# Shc_Encoder_Optic_Sensor.net
KiCad netlist of a schematic drawn in Altium Designer
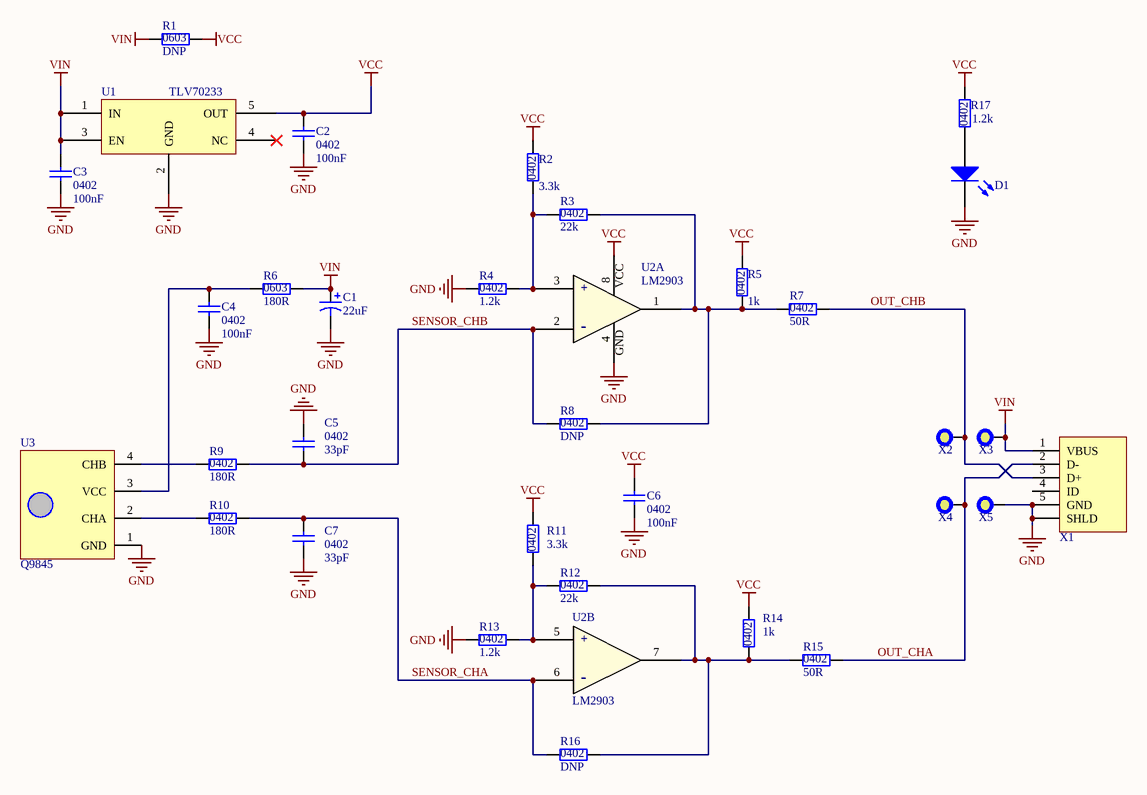
[diagram p0: Shc_Encoder_Optic_Sensor.SchDoc]

(export (version "E")
  (design (tool "Eeschema 10.0.6"))
  (components
    (comp (ref "C1")
      (value "22uF")
      (footprint "TCAP SMA")
      (description "Tantal Capacitor SMA")
      (fields (field (name "Comment") "TCAP CASE A"))
      (libsource (lib "CAP") (part "TCAP CASE A"))
    )
    (comp (ref "C2")
      (value "100nF")
      (footprint "C0402-h0.5-O")
      (description "Multilayer ceramic capacitors  0402")
      (fields
        (field (name "CASE") "0402")
        (field (name "Comment") "Ceramic Capacitor X7R 10% 50V")
        (field (name "DESIGNER") "Crom")
      )
      (libsource (lib "CAP") (part "Cap CER 0402 S"))
    )
    (comp (ref "C3")
      (value "100nF")
      (footprint "C0402-h0.5-O")
      (description "Multilayer ceramic capacitors  0402")
      (fields
        (field (name "CASE") "0402")
        (field (name "Comment") "Ceramic Capacitor X7R 10% 50V")
        (field (name "DESIGNER") "Crom")
      )
      (libsource (lib "CAP") (part "Cap CER 0402 S"))
    )
    (comp (ref "C4")
      (value "100nF")
      (footprint "C0402-h0.5-O")
      (description "Multilayer ceramic capacitors  0402")
      (fields
        (field (name "CASE") "0402")
        (field (name "Comment") "Ceramic Capacitor X7R 10% 50V")
        (field (name "DESIGNER") "Crom")
      )
      (libsource (lib "CAP") (part "Cap CER 0402 S"))
    )
    (comp (ref "C5")
      (value "33pF")
      (footprint "C0402-h0.5-O")
      (description "Multilayer ceramic capacitors  0402")
      (fields
        (field (name "CASE") "0402")
        (field (name "Comment") "Ceramic Capacitor X7R 10% 50V")
        (field (name "DESIGNER") "Crom")
      )
      (libsource (lib "CAP") (part "Cap CER 0402 S"))
    )
    (comp (ref "C6")
      (value "100nF")
      (footprint "C0402-h0.5-O")
      (description "Multilayer ceramic capacitors  0402")
      (fields
        (field (name "CASE") "0402")
        (field (name "Comment") "Ceramic Capacitor X7R 10% 50V")
        (field (name "DESIGNER") "Crom")
      )
      (libsource (lib "CAP") (part "Cap CER 0402 S"))
    )
    (comp (ref "C7")
      (value "33pF")
      (footprint "C0402-h0.5-O")
      (description "Multilayer ceramic capacitors  0402")
      (fields
        (field (name "CASE") "0402")
        (field (name "Comment") "Ceramic Capacitor X7R 10% 50V")
        (field (name "DESIGNER") "Crom")
      )
      (libsource (lib "CAP") (part "Cap CER 0402 S"))
    )
    (comp (ref "D1")
      (value "LED 0603")
      (footprint "LED 0603_RED")
      (description "Typical SMT LED")
      (libsource (lib "OPTO") (part "LED 0603"))
    )
    (comp (ref "R1")
      (value "DNP")
      (footprint "R0603")
      (description "Chip Resistor 0603 (1608)")
      (fields
        (field (name "CASE") "0603")
        (field (name "Comment") "Thick Film Resistor 0603 5%")
        (field (name "DESIGNER") "Crom")
      )
      (libsource (lib "RES") (part "Res 0603"))
    )
    (comp (ref "R2")
      (value "3.3k")
      (footprint "R0402-O")
      (description "Chip Resistor 0402 (1005) 1/16W")
      (fields
        (field (name "CASE") "0402")
        (field (name "Comment") "Thick Film Resistor 0402 5%")
        (field (name "DESIGNER") "Crom")
      )
      (libsource (lib "") (part "Res 0402_1"))
    )
    (comp (ref "R3")
      (value "22k")
      (footprint "R0402-O")
      (description "Chip Resistor 0402 (1005) 1/16W")
      (fields
        (field (name "CASE") "0402")
        (field (name "Comment") "Thick Film Resistor 0402 5%")
        (field (name "DESIGNER") "Crom")
      )
      (libsource (lib "RES") (part "Res 0402"))
    )
    (comp (ref "R4")
      (value "1.2k")
      (footprint "R0402-O")
      (description "Chip Resistor 0402 (1005) 1/16W")
      (fields
        (field (name "CASE") "0402")
        (field (name "Comment") "Thick Film Resistor 0402 5%")
        (field (name "DESIGNER") "Crom")
      )
      (libsource (lib "RES") (part "Res 0402"))
    )
    (comp (ref "R5")
      (value "1k")
      (footprint "R0402-O")
      (description "Chip Resistor 0402 (1005) 1/16W")
      (fields
        (field (name "CASE") "0402")
        (field (name "Comment") "Thick Film Resistor 0402 5%")
        (field (name "DESIGNER") "Crom")
      )
      (libsource (lib "") (part "Res 0402_1"))
    )
    (comp (ref "R6")
      (value "180R")
      (footprint "R0603")
      (description "Chip Resistor 0603 (1608)")
      (fields
        (field (name "CASE") "0603")
        (field (name "Comment") "Thick Film Resistor 0603 5%")
        (field (name "DESIGNER") "Crom")
      )
      (libsource (lib "RES") (part "Res 0603"))
    )
    (comp (ref "R7")
      (value "50R")
      (footprint "R0402-O")
      (description "Chip Resistor 0402 (1005) 1/16W")
      (fields
        (field (name "CASE") "0402")
        (field (name "Comment") "Thick Film Resistor 0402 5%")
        (field (name "DESIGNER") "Crom")
      )
      (libsource (lib "RES") (part "Res 0402"))
    )
    (comp (ref "R8")
      (value "DNP")
      (footprint "R0402-O")
      (description "Chip Resistor 0402 (1005) 1/16W")
      (fields
        (field (name "CASE") "0402")
        (field (name "Comment") "Thick Film Resistor 0402 5%")
        (field (name "DESIGNER") "Crom")
      )
      (libsource (lib "RES") (part "Res 0402"))
    )
    (comp (ref "R9")
      (value "180R")
      (footprint "R0402-O")
      (description "Chip Resistor 0402 (1005) 1/16W")
      (fields
        (field (name "CASE") "0402")
        (field (name "Comment") "Thick Film Resistor 0402 5%")
        (field (name "DESIGNER") "Crom")
      )
      (libsource (lib "RES") (part "Res 0402"))
    )
    (comp (ref "R10")
      (value "180R")
      (footprint "R0402-O")
      (description "Chip Resistor 0402 (1005) 1/16W")
      (fields
        (field (name "CASE") "0402")
        (field (name "Comment") "Thick Film Resistor 0402 5%")
        (field (name "DESIGNER") "Crom")
      )
      (libsource (lib "RES") (part "Res 0402"))
    )
    (comp (ref "R11")
      (value "3.3k")
      (footprint "R0402-O")
      (description "Chip Resistor 0402 (1005) 1/16W")
      (fields
        (field (name "CASE") "0402")
        (field (name "Comment") "Thick Film Resistor 0402 5%")
        (field (name "DESIGNER") "Crom")
      )
      (libsource (lib "") (part "Res 0402_1"))
    )
    (comp (ref "R12")
      (value "22k")
      (footprint "R0402-O")
      (description "Chip Resistor 0402 (1005) 1/16W")
      (fields
        (field (name "CASE") "0402")
        (field (name "Comment") "Thick Film Resistor 0402 5%")
        (field (name "DESIGNER") "Crom")
      )
      (libsource (lib "RES") (part "Res 0402"))
    )
    (comp (ref "R13")
      (value "1.2k")
      (footprint "R0402-O")
      (description "Chip Resistor 0402 (1005) 1/16W")
      (fields
        (field (name "CASE") "0402")
        (field (name "Comment") "Thick Film Resistor 0402 5%")
        (field (name "DESIGNER") "Crom")
      )
      (libsource (lib "RES") (part "Res 0402"))
    )
    (comp (ref "R14")
      (value "1k")
      (footprint "R0402-O")
      (description "Chip Resistor 0402 (1005) 1/16W")
      (fields
        (field (name "CASE") "0402")
        (field (name "Comment") "Thick Film Resistor 0402 5%")
        (field (name "DESIGNER") "Crom")
      )
      (libsource (lib "") (part "Res 0402_1"))
    )
    (comp (ref "R15")
      (value "50R")
      (footprint "R0402-O")
      (description "Chip Resistor 0402 (1005) 1/16W")
      (fields
        (field (name "CASE") "0402")
        (field (name "Comment") "Thick Film Resistor 0402 5%")
        (field (name "DESIGNER") "Crom")
      )
      (libsource (lib "RES") (part "Res 0402"))
    )
    (comp (ref "R16")
      (value "DNP")
      (footprint "R0402-O")
      (description "Chip Resistor 0402 (1005) 1/16W")
      (fields
        (field (name "CASE") "0402")
        (field (name "Comment") "Thick Film Resistor 0402 5%")
        (field (name "DESIGNER") "Crom")
      )
      (libsource (lib "RES") (part "Res 0402"))
    )
    (comp (ref "R17")
      (value "1.2k")
      (footprint "R0402-O")
      (description "Chip Resistor 0402 (1005) 1/16W")
      (fields
        (field (name "CASE") "0402")
        (field (name "Comment") "Thick Film Resistor 0402 5%")
        (field (name "DESIGNER") "Crom")
      )
      (libsource (lib "") (part "Res 0402_2"))
    )
    (comp (ref "U1")
      (value "TLV70233")
      (footprint "SOT-23-5")
      (description "LDO 3.3V 300mA")
      (libsource (lib "LDO") (part "TLV70233"))
    )
    (comp (ref "U2")
      (value "LM2903")
      (footprint "SOIC-8-150")
      (description "Dual Differential Comparators")
      (libsource (lib "IC") (part "LM293 / LM2903"))
    )
    (comp (ref "U3")
      (value "Q9845")
      (footprint "SENSOR_OPTO-Encoder Rp")
      (description "Small Optical Encoder Module (HEDS-97xx)")
      (libsource (lib "SENSORS") (part "Optic_Encoder_Sensor"))
    )
    (comp (ref "X1")
      (value "ZX62-AB-5PA(11)")
      (footprint "USB_micro_TH")
      (description "USB micro AB SMT R/A")
      (libsource (lib "CONNECTORS") (part "USB_micro"))
    )
    (comp (ref "X2")
      (value "PAD_C_1.2MM")
      (footprint "PAD_C_1.2mm")
      (description "1x1x0.8mm hole")
      (libsource (lib "CONNECTORS") (part "PAD_1.2MM"))
    )
    (comp (ref "X3")
      (value "PAD_C_1.2MM")
      (footprint "PAD_C_1.2mm")
      (description "1x1x0.8mm hole")
      (libsource (lib "CONNECTORS") (part "PAD_1.2MM"))
    )
    (comp (ref "X4")
      (value "PAD_C_1.2MM")
      (footprint "PAD_C_1.2mm")
      (description "1x1x0.8mm hole")
      (libsource (lib "CONNECTORS") (part "PAD_1.2MM"))
    )
    (comp (ref "X5")
      (value "PAD_C_1.2MM")
      (footprint "PAD_C_1.2mm")
      (description "1x1x0.8mm hole")
      (libsource (lib "CONNECTORS") (part "PAD_1.2MM"))
    )
  )
  (nets
    (net (code "1") (name "/OUT_CHA") (class "Default")
      (node (ref "R15") (pin "2") (pinfunction "2_2") (pintype "passive"))
      (node (ref "X1") (pin "2") (pinfunction "D-_2") (pintype "passive"))
      (node (ref "X4") (pin "1") (pinfunction "1_1") (pintype "passive"))
    )
    (net (code "2") (name "/OUT_CHB") (class "Default")
      (node (ref "R7") (pin "2") (pinfunction "2_2") (pintype "passive"))
      (node (ref "X1") (pin "3") (pinfunction "D+_3") (pintype "passive"))
      (node (ref "X2") (pin "1") (pinfunction "1_1") (pintype "passive"))
    )
    (net (code "3") (name "/SENSOR_CHA") (class "Default")
      (node (ref "C7") (pin "2") (pinfunction "2_2") (pintype "passive"))
      (node (ref "R10") (pin "2") (pinfunction "2_2") (pintype "passive"))
      (node (ref "R16") (pin "1") (pinfunction "1_1") (pintype "passive"))
      (node (ref "U2") (pin "6") (pinfunction "2IN-_6") (pintype "passive"))
    )
    (net (code "4") (name "/SENSOR_CHB") (class "Default")
      (node (ref "C5") (pin "2") (pinfunction "2_2") (pintype "passive"))
      (node (ref "R8") (pin "1") (pinfunction "1_1") (pintype "passive"))
      (node (ref "R9") (pin "2") (pinfunction "2_2") (pintype "passive"))
      (node (ref "U2") (pin "2") (pinfunction "1IN-_2") (pintype "passive"))
    )
    (net (code "5") (name "GND") (class "Default")
      (node (ref "C1") (pin "-") (pinfunction "-_-") (pintype "passive"))
      (node (ref "C2") (pin "1") (pinfunction "1_1") (pintype "passive"))
      (node (ref "C3") (pin "1") (pinfunction "1_1") (pintype "passive"))
      (node (ref "C4") (pin "1") (pinfunction "1_1") (pintype "passive"))
      (node (ref "C5") (pin "1") (pinfunction "1_1") (pintype "passive"))
      (node (ref "C6") (pin "1") (pinfunction "1_1") (pintype "passive"))
      (node (ref "C7") (pin "1") (pinfunction "1_1") (pintype "passive"))
      (node (ref "D1") (pin "2") (pinfunction "K_2") (pintype "passive"))
      (node (ref "R13") (pin "1") (pinfunction "1_1") (pintype "passive"))
      (node (ref "R4") (pin "1") (pinfunction "1_1") (pintype "passive"))
      (node (ref "U1") (pin "2") (pinfunction "GND_2") (pintype "passive"))
      (node (ref "U2") (pin "4") (pinfunction "GND_4") (pintype "passive"))
      (node (ref "U3") (pin "1") (pinfunction "GND_1") (pintype "passive"))
      (node (ref "X1") (pin "5") (pinfunction "GND_5") (pintype "power_in"))
      (node (ref "X1") (pin "SH") (pinfunction "SHLD_SH") (pintype "power_in"))
      (node (ref "X5") (pin "1") (pinfunction "1_1") (pintype "passive"))
    )
    (net (code "6") (name "Net-(D1-A)") (class "Default")
      (node (ref "D1") (pin "1") (pinfunction "A_1") (pintype "passive"))
      (node (ref "R17") (pin "1") (pinfunction "1_1") (pintype "passive"))
    )
    (net (code "7") (name "Net-(U2A-1IN+)") (class "Default")
      (node (ref "R2") (pin "2") (pinfunction "2_2") (pintype "passive"))
      (node (ref "R3") (pin "1") (pinfunction "1_1") (pintype "passive"))
      (node (ref "R4") (pin "2") (pinfunction "2_2") (pintype "passive"))
      (node (ref "U2") (pin "3") (pinfunction "1IN+_3") (pintype "passive"))
    )
    (net (code "8") (name "Net-(U2A-1OUT)") (class "Default")
      (node (ref "R3") (pin "2") (pinfunction "2_2") (pintype "passive"))
      (node (ref "R5") (pin "2") (pinfunction "2_2") (pintype "passive"))
      (node (ref "R7") (pin "1") (pinfunction "1_1") (pintype "passive"))
      (node (ref "R8") (pin "2") (pinfunction "2_2") (pintype "passive"))
      (node (ref "U2") (pin "1") (pinfunction "1OUT_1") (pintype "passive"))
    )
    (net (code "9") (name "Net-(U2B-2IN+)") (class "Default")
      (node (ref "R11") (pin "2") (pinfunction "2_2") (pintype "passive"))
      (node (ref "R12") (pin "1") (pinfunction "1_1") (pintype "passive"))
      (node (ref "R13") (pin "2") (pinfunction "2_2") (pintype "passive"))
      (node (ref "U2") (pin "5") (pinfunction "2IN+_5") (pintype "passive"))
    )
    (net (code "10") (name "Net-(U2B-2OUT)") (class "Default")
      (node (ref "R12") (pin "2") (pinfunction "2_2") (pintype "passive"))
      (node (ref "R14") (pin "2") (pinfunction "2_2") (pintype "passive"))
      (node (ref "R15") (pin "1") (pinfunction "1_1") (pintype "passive"))
      (node (ref "R16") (pin "2") (pinfunction "2_2") (pintype "passive"))
      (node (ref "U2") (pin "7") (pinfunction "2OUT_7") (pintype "passive"))
    )
    (net (code "11") (name "Net-(U3-CHA)") (class "Default")
      (node (ref "R10") (pin "1") (pinfunction "1_1") (pintype "passive"))
      (node (ref "U3") (pin "2") (pinfunction "CHA_2") (pintype "passive"))
    )
    (net (code "12") (name "Net-(U3-CHB)") (class "Default")
      (node (ref "R9") (pin "1") (pinfunction "1_1") (pintype "passive"))
      (node (ref "U3") (pin "4") (pinfunction "CHB_4") (pintype "passive"))
    )
    (net (code "13") (name "Net-(U3-VCC)") (class "Default")
      (node (ref "C4") (pin "2") (pinfunction "2_2") (pintype "passive"))
      (node (ref "R6") (pin "1") (pinfunction "1_1") (pintype "passive"))
      (node (ref "U3") (pin "3") (pinfunction "VCC_3") (pintype "passive"))
    )
    (net (code "14") (name "VCC") (class "Default")
      (node (ref "C2") (pin "2") (pinfunction "2_2") (pintype "passive"))
      (node (ref "C6") (pin "2") (pinfunction "2_2") (pintype "passive"))
      (node (ref "R1") (pin "2") (pinfunction "2_2") (pintype "passive"))
      (node (ref "R11") (pin "1") (pinfunction "1_1") (pintype "passive"))
      (node (ref "R14") (pin "1") (pinfunction "1_1") (pintype "passive"))
      (node (ref "R17") (pin "2") (pinfunction "2_2") (pintype "passive"))
      (node (ref "R2") (pin "1") (pinfunction "1_1") (pintype "passive"))
      (node (ref "R5") (pin "1") (pinfunction "1_1") (pintype "passive"))
      (node (ref "U1") (pin "5") (pinfunction "OUT_5") (pintype "passive"))
      (node (ref "U2") (pin "8") (pinfunction "VCC_8") (pintype "passive"))
    )
    (net (code "15") (name "VIN") (class "Default")
      (node (ref "C1") (pin "+") (pinfunction "+_+") (pintype "passive"))
      (node (ref "C3") (pin "2") (pinfunction "2_2") (pintype "passive"))
      (node (ref "R1") (pin "1") (pinfunction "1_1") (pintype "passive"))
      (node (ref "R6") (pin "2") (pinfunction "2_2") (pintype "passive"))
      (node (ref "U1") (pin "1") (pinfunction "IN_1") (pintype "passive"))
      (node (ref "U1") (pin "3") (pinfunction "EN_3") (pintype "passive"))
      (node (ref "X1") (pin "1") (pinfunction "VBUS_1") (pintype "power_in"))
      (node (ref "X3") (pin "1") (pinfunction "1_1") (pintype "passive"))
    )
    (net (code "16") (name "unconnected-(U1-NC-Pad4)") (class "Default")
      (node (ref "U1") (pin "4") (pinfunction "NC_4") (pintype "passive+no_connect"))
    )
    (net (code "17") (name "unconnected-(X1-ID-Pad4)") (class "Default")
      (node (ref "X1") (pin "4") (pinfunction "ID_4") (pintype "passive"))
    )
  )
)
